# HDMI_DLT.net
KiCad netlist of a schematic drawn in EAGLE
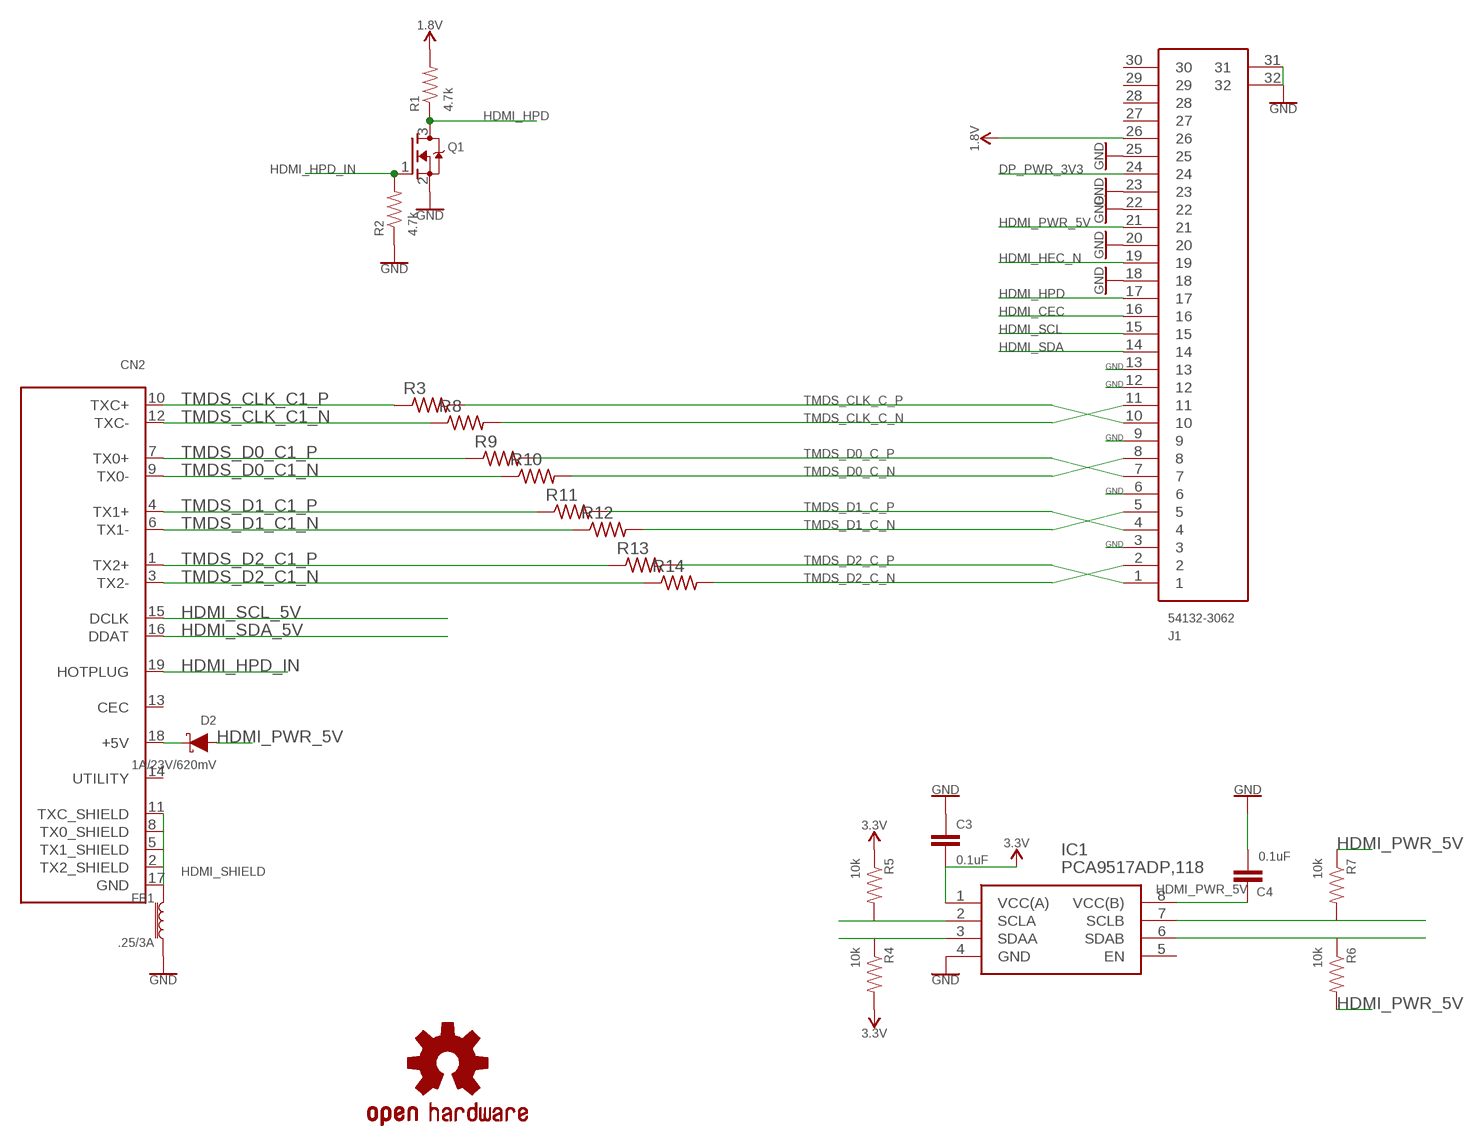
[diagram p0: schematic, sheet 1]

(export (version "E")
  (design (tool "Eeschema 10.0.6"))
  (components
    (comp (ref "C3")
      (value "0.1uF")
      (footprint "eagle-import:0603")
      (libsource (lib "eagle-import") (part "10NF-0603-50V-10%"))
    )
    (comp (ref "C4")
      (value "0.1uF")
      (footprint "eagle-import:0603")
      (libsource (lib "eagle-import") (part "10NF-0603-50V-10%"))
    )
    (comp (ref "CN2")
      (value "HDMI_MOLEX_47151-0001")
      (footprint "eagle-import:HDMI_MOLEX_47151-0001")
      (libsource (lib "eagle-import") (part "HDMI_MOLEX_47151-0001"))
    )
    (comp (ref "D2")
      (value "1A/23V/620mV")
      (footprint "eagle-import:SOD-323")
      (libsource (lib "eagle-import") (part "DIODE-SCHOTTKY-BAT20J"))
    )
    (comp (ref "FB1")
      (value ".25/3A")
      (footprint "eagle-import:0603")
      (libsource (lib "eagle-import") (part "FERRITE_BEAD-0603"))
    )
    (comp (ref "IC1")
      (value "PCA9517ADP,118")
      (footprint "eagle-import:SOP65P490X110-8N")
      (fields (field (name "MOUSER_PART_NUMBER") "771-PCA9517ADP118"))
      (libsource (lib "eagle-import") (part "PCA9517ADP,118"))
    )
    (comp (ref "J1")
      (value "54132-3062")
      (footprint "eagle-import:54132-3062")
      (fields (field (name "MOUSER_PART_NUMBER") "538-54132-3062"))
      (libsource (lib "eagle-import") (part "54132-3062"))
    )
    (comp (ref "LOGO1")
      (value "OSHW-LOGOS-COPPER")
      (footprint "eagle-import:OSHW-LOGO-S_COPPER")
      (libsource (lib "eagle-import") (part "OSHW-LOGOS-COPPER"))
    )
    (comp (ref "Q1")
      (value "MOSFET-NWAVE")
      (footprint "eagle-import:SOT23-W")
      (libsource (lib "eagle-import") (part "MOSFET-NWAVE"))
    )
    (comp (ref "R1")
      (value "4.7k")
      (footprint "eagle-import:0805")
      (libsource (lib "eagle-import") (part "RESISTOR0805-RES"))
    )
    (comp (ref "R2")
      (value "4.7k")
      (footprint "eagle-import:0805")
      (libsource (lib "eagle-import") (part "RESISTOR0805-RES"))
    )
    (comp (ref "R3")
      (value "R-US_R0402")
      (footprint "eagle-import:R0402")
      (libsource (lib "eagle-import") (part "R-US_R0402"))
    )
    (comp (ref "R4")
      (value "10k")
      (footprint "eagle-import:0805")
      (libsource (lib "eagle-import") (part "RESISTOR0805-RES"))
    )
    (comp (ref "R5")
      (value "10k")
      (footprint "eagle-import:0805")
      (libsource (lib "eagle-import") (part "RESISTOR0805-RES"))
    )
    (comp (ref "R6")
      (value "10k")
      (footprint "eagle-import:0805")
      (libsource (lib "eagle-import") (part "RESISTOR0805-RES"))
    )
    (comp (ref "R7")
      (value "10k")
      (footprint "eagle-import:0805")
      (libsource (lib "eagle-import") (part "RESISTOR0805-RES"))
    )
    (comp (ref "R8")
      (value "R-US_R0402")
      (footprint "eagle-import:R0402")
      (libsource (lib "eagle-import") (part "R-US_R0402"))
    )
    (comp (ref "R9")
      (value "R-US_R0402")
      (footprint "eagle-import:R0402")
      (libsource (lib "eagle-import") (part "R-US_R0402"))
    )
    (comp (ref "R10")
      (value "R-US_R0402")
      (footprint "eagle-import:R0402")
      (libsource (lib "eagle-import") (part "R-US_R0402"))
    )
    (comp (ref "R11")
      (value "R-US_R0402")
      (footprint "eagle-import:R0402")
      (libsource (lib "eagle-import") (part "R-US_R0402"))
    )
    (comp (ref "R12")
      (value "R-US_R0402")
      (footprint "eagle-import:R0402")
      (libsource (lib "eagle-import") (part "R-US_R0402"))
    )
    (comp (ref "R13")
      (value "R-US_R0402")
      (footprint "eagle-import:R0402")
      (libsource (lib "eagle-import") (part "R-US_R0402"))
    )
    (comp (ref "R14")
      (value "R-US_R0402")
      (footprint "eagle-import:R0402")
      (libsource (lib "eagle-import") (part "R-US_R0402"))
    )
  )
  (nets
    (net (code "1") (name "/DP_PWR_3V3") (class "Default")
      (node (ref "J1") (pin "24") (pinfunction "24_24") (pintype "bidirectional"))
    )
    (net (code "2") (name "/HDMI_CEC") (class "Default")
      (node (ref "J1") (pin "16") (pinfunction "16_16") (pintype "bidirectional"))
    )
    (net (code "3") (name "/HDMI_HEC_N") (class "Default")
      (node (ref "J1") (pin "19") (pinfunction "19_19") (pintype "bidirectional"))
    )
    (net (code "4") (name "/HDMI_HPD") (class "Default")
      (node (ref "J1") (pin "17") (pinfunction "17_17") (pintype "bidirectional"))
      (node (ref "Q1") (pin "3") (pinfunction "D_3") (pintype "bidirectional"))
      (node (ref "R1") (pin "1") (pinfunction "1_1") (pintype "passive"))
    )
    (net (code "5") (name "/HDMI_HPD_IN") (class "Default")
      (node (ref "CN2") (pin "19") (pinfunction "HOTPLUG_19") (pintype "bidirectional"))
      (node (ref "Q1") (pin "1") (pinfunction "G_1") (pintype "bidirectional"))
      (node (ref "R2") (pin "2") (pinfunction "2_2") (pintype "passive"))
    )
    (net (code "6") (name "/HDMI_PWR_5V") (class "Default")
      (node (ref "C4") (pin "1") (pinfunction "1_1") (pintype "passive"))
      (node (ref "D2") (pin "A") (pinfunction "A_A") (pintype "passive"))
      (node (ref "IC1") (pin "8") (pinfunction "VCC(B)_8") (pintype "bidirectional"))
      (node (ref "J1") (pin "21") (pinfunction "21_21") (pintype "bidirectional"))
      (node (ref "R6") (pin "2") (pinfunction "2_2") (pintype "passive"))
      (node (ref "R7") (pin "1") (pinfunction "1_1") (pintype "passive"))
    )
    (net (code "7") (name "/HDMI_SCL") (class "Default")
      (node (ref "IC1") (pin "2") (pinfunction "SCLA_2") (pintype "bidirectional"))
      (node (ref "J1") (pin "15") (pinfunction "15_15") (pintype "bidirectional"))
      (node (ref "R5") (pin "2") (pinfunction "2_2") (pintype "passive"))
    )
    (net (code "8") (name "/HDMI_SCL_5V") (class "Default")
      (node (ref "CN2") (pin "15") (pinfunction "DCLK_15") (pintype "bidirectional"))
      (node (ref "IC1") (pin "7") (pinfunction "SCLB_7") (pintype "bidirectional"))
      (node (ref "R7") (pin "2") (pinfunction "2_2") (pintype "passive"))
    )
    (net (code "9") (name "/HDMI_SDA") (class "Default")
      (node (ref "IC1") (pin "3") (pinfunction "SDAA_3") (pintype "bidirectional"))
      (node (ref "J1") (pin "14") (pinfunction "14_14") (pintype "bidirectional"))
      (node (ref "R4") (pin "1") (pinfunction "1_1") (pintype "passive"))
    )
    (net (code "10") (name "/HDMI_SDA_5V") (class "Default")
      (node (ref "CN2") (pin "16") (pinfunction "DDAT_16") (pintype "bidirectional"))
      (node (ref "IC1") (pin "6") (pinfunction "SDAB_6") (pintype "bidirectional"))
      (node (ref "R6") (pin "1") (pinfunction "1_1") (pintype "passive"))
    )
    (net (code "11") (name "/HDMI_SHIELD") (class "Default")
      (node (ref "CN2") (pin "11") (pinfunction "TXC_SHIELD_11") (pintype "power_in"))
      (node (ref "CN2") (pin "17") (pinfunction "GND_17") (pintype "power_in"))
      (node (ref "CN2") (pin "2") (pinfunction "TX2_SHIELD_2") (pintype "power_in"))
      (node (ref "CN2") (pin "5") (pinfunction "TX1_SHIELD_5") (pintype "power_in"))
      (node (ref "CN2") (pin "8") (pinfunction "TX0_SHIELD_8") (pintype "power_in"))
      (node (ref "FB1") (pin "1") (pinfunction "1_1") (pintype "passive"))
    )
    (net (code "12") (name "/TMDS_CLK_C1_N") (class "Default")
      (node (ref "CN2") (pin "12") (pinfunction "TXC-_12") (pintype "bidirectional"))
      (node (ref "R8") (pin "1") (pinfunction "1_1") (pintype "passive"))
    )
    (net (code "13") (name "/TMDS_CLK_C1_P") (class "Default")
      (node (ref "CN2") (pin "10") (pinfunction "TXC+_10") (pintype "bidirectional"))
      (node (ref "R3") (pin "1") (pinfunction "1_1") (pintype "passive"))
    )
    (net (code "14") (name "/TMDS_CLK_C_N") (class "Default")
      (node (ref "J1") (pin "11") (pinfunction "11_11") (pintype "bidirectional"))
      (node (ref "R8") (pin "2") (pinfunction "2_2") (pintype "passive"))
    )
    (net (code "15") (name "/TMDS_CLK_C_P") (class "Default")
      (node (ref "J1") (pin "10") (pinfunction "10_10") (pintype "bidirectional"))
      (node (ref "R3") (pin "2") (pinfunction "2_2") (pintype "passive"))
    )
    (net (code "16") (name "/TMDS_D0_C1_N") (class "Default")
      (node (ref "CN2") (pin "9") (pinfunction "TX0-_9") (pintype "bidirectional"))
      (node (ref "R10") (pin "1") (pinfunction "1_1") (pintype "passive"))
    )
    (net (code "17") (name "/TMDS_D0_C1_P") (class "Default")
      (node (ref "CN2") (pin "7") (pinfunction "TX0+_7") (pintype "bidirectional"))
      (node (ref "R9") (pin "1") (pinfunction "1_1") (pintype "passive"))
    )
    (net (code "18") (name "/TMDS_D0_C_N") (class "Default")
      (node (ref "J1") (pin "8") (pinfunction "8_8") (pintype "bidirectional"))
      (node (ref "R10") (pin "2") (pinfunction "2_2") (pintype "passive"))
    )
    (net (code "19") (name "/TMDS_D0_C_P") (class "Default")
      (node (ref "J1") (pin "7") (pinfunction "7_7") (pintype "bidirectional"))
      (node (ref "R9") (pin "2") (pinfunction "2_2") (pintype "passive"))
    )
    (net (code "20") (name "/TMDS_D1_C1_N") (class "Default")
      (node (ref "CN2") (pin "6") (pinfunction "TX1-_6") (pintype "bidirectional"))
      (node (ref "R12") (pin "1") (pinfunction "1_1") (pintype "passive"))
    )
    (net (code "21") (name "/TMDS_D1_C1_P") (class "Default")
      (node (ref "CN2") (pin "4") (pinfunction "TX1+_4") (pintype "bidirectional"))
      (node (ref "R11") (pin "1") (pinfunction "1_1") (pintype "passive"))
    )
    (net (code "22") (name "/TMDS_D1_C_N") (class "Default")
      (node (ref "J1") (pin "5") (pinfunction "5_5") (pintype "bidirectional"))
      (node (ref "R12") (pin "2") (pinfunction "2_2") (pintype "passive"))
    )
    (net (code "23") (name "/TMDS_D1_C_P") (class "Default")
      (node (ref "J1") (pin "4") (pinfunction "4_4") (pintype "bidirectional"))
      (node (ref "R11") (pin "2") (pinfunction "2_2") (pintype "passive"))
    )
    (net (code "24") (name "/TMDS_D2_C1_N") (class "Default")
      (node (ref "CN2") (pin "3") (pinfunction "TX2-_3") (pintype "bidirectional"))
      (node (ref "R14") (pin "1") (pinfunction "1_1") (pintype "passive"))
    )
    (net (code "25") (name "/TMDS_D2_C1_P") (class "Default")
      (node (ref "CN2") (pin "1") (pinfunction "TX2+_1") (pintype "bidirectional"))
      (node (ref "R13") (pin "1") (pinfunction "1_1") (pintype "passive"))
    )
    (net (code "26") (name "/TMDS_D2_C_N") (class "Default")
      (node (ref "J1") (pin "2") (pinfunction "2_2") (pintype "bidirectional"))
      (node (ref "R14") (pin "2") (pinfunction "2_2") (pintype "passive"))
    )
    (net (code "27") (name "/TMDS_D2_C_P") (class "Default")
      (node (ref "J1") (pin "1") (pinfunction "1_1") (pintype "bidirectional"))
      (node (ref "R13") (pin "2") (pinfunction "2_2") (pintype "passive"))
    )
    (net (code "28") (name "1.8V") (class "Default")
      (node (ref "J1") (pin "26") (pinfunction "26_26") (pintype "bidirectional"))
      (node (ref "R1") (pin "2") (pinfunction "2_2") (pintype "passive"))
    )
    (net (code "29") (name "3.3V") (class "Default")
      (node (ref "C3") (pin "2") (pinfunction "2_2") (pintype "passive"))
      (node (ref "IC1") (pin "1") (pinfunction "VCC(A)_1") (pintype "bidirectional"))
      (node (ref "R4") (pin "2") (pinfunction "2_2") (pintype "passive"))
      (node (ref "R5") (pin "1") (pinfunction "1_1") (pintype "passive"))
    )
    (net (code "30") (name "GND") (class "Default")
      (node (ref "C3") (pin "1") (pinfunction "1_1") (pintype "passive"))
      (node (ref "C4") (pin "2") (pinfunction "2_2") (pintype "passive"))
      (node (ref "FB1") (pin "2") (pinfunction "2_2") (pintype "passive"))
      (node (ref "IC1") (pin "4") (pinfunction "GND_4") (pintype "bidirectional"))
      (node (ref "J1") (pin "12") (pinfunction "12_12") (pintype "bidirectional"))
      (node (ref "J1") (pin "13") (pinfunction "13_13") (pintype "bidirectional"))
      (node (ref "J1") (pin "18") (pinfunction "18_18") (pintype "bidirectional"))
      (node (ref "J1") (pin "20") (pinfunction "20_20") (pintype "bidirectional"))
      (node (ref "J1") (pin "22") (pinfunction "22_22") (pintype "bidirectional"))
      (node (ref "J1") (pin "23") (pinfunction "23_23") (pintype "bidirectional"))
      (node (ref "J1") (pin "25") (pinfunction "25_25") (pintype "bidirectional"))
      (node (ref "J1") (pin "3") (pinfunction "3_3") (pintype "bidirectional"))
      (node (ref "J1") (pin "31") (pinfunction "31_31") (pintype "bidirectional"))
      (node (ref "J1") (pin "32") (pinfunction "32_32") (pintype "bidirectional"))
      (node (ref "J1") (pin "6") (pinfunction "6_6") (pintype "bidirectional"))
      (node (ref "J1") (pin "9") (pinfunction "9_9") (pintype "bidirectional"))
      (node (ref "Q1") (pin "2") (pinfunction "S_2") (pintype "bidirectional"))
      (node (ref "R2") (pin "1") (pinfunction "1_1") (pintype "passive"))
    )
    (net (code "31") (name "Net-(CN2A-+5V)") (class "Default")
      (node (ref "CN2") (pin "18") (pinfunction "+5V_18") (pintype "power_in"))
      (node (ref "D2") (pin "C") (pinfunction "C_C") (pintype "passive"))
    )
    (net (code "32") (name "unconnected-(CN2A-CEC-Pad13)") (class "Default")
      (node (ref "CN2") (pin "13") (pinfunction "CEC_13") (pintype "bidirectional"))
    )
    (net (code "33") (name "unconnected-(CN2A-UTILITY-Pad14)") (class "Default")
      (node (ref "CN2") (pin "14") (pinfunction "UTILITY_14") (pintype "bidirectional"))
    )
    (net (code "34") (name "unconnected-(IC1-EN-Pad5)") (class "Default")
      (node (ref "IC1") (pin "5") (pinfunction "EN_5") (pintype "bidirectional"))
    )
    (net (code "35") (name "unconnected-(J1-Pad27)") (class "Default")
      (node (ref "J1") (pin "27") (pinfunction "27_27") (pintype "bidirectional"))
    )
    (net (code "36") (name "unconnected-(J1-Pad28)") (class "Default")
      (node (ref "J1") (pin "28") (pinfunction "28_28") (pintype "bidirectional"))
    )
    (net (code "37") (name "unconnected-(J1-Pad29)") (class "Default")
      (node (ref "J1") (pin "29") (pinfunction "29_29") (pintype "bidirectional"))
    )
    (net (code "38") (name "unconnected-(J1-Pad30)") (class "Default")
      (node (ref "J1") (pin "30") (pinfunction "30_30") (pintype "bidirectional"))
    )
  )
)
